# Sensors.net
KiCad netlist of a schematic drawn in Altium Designer
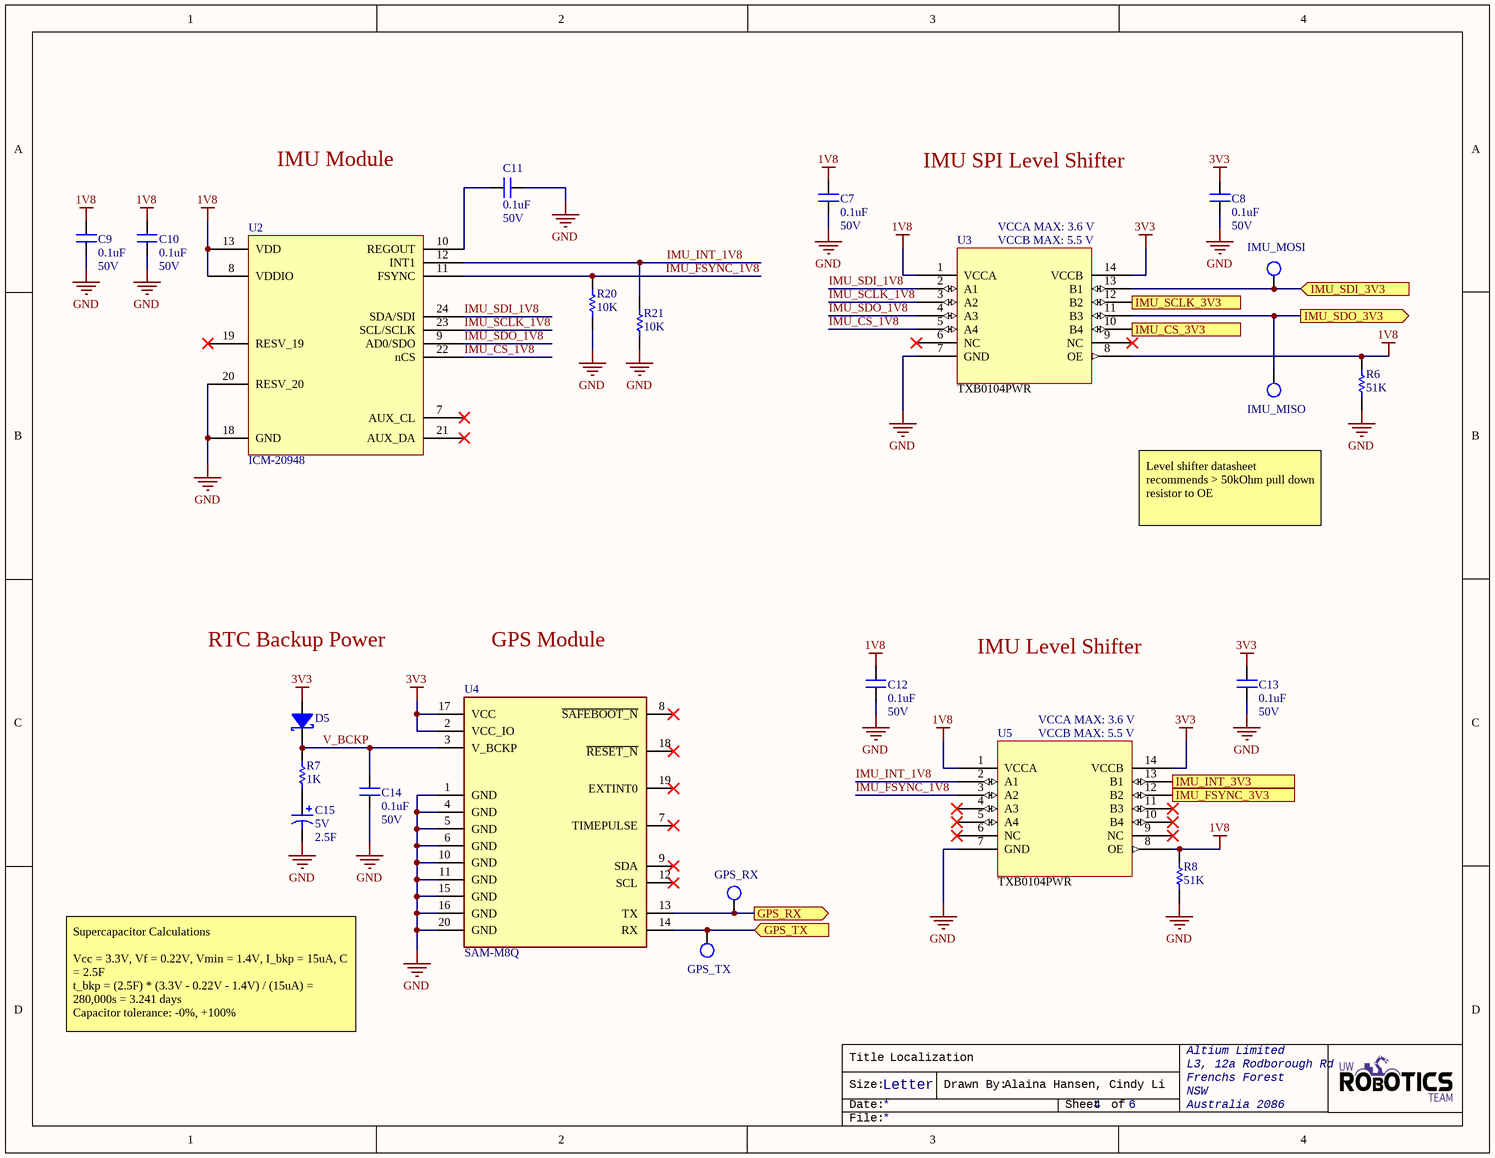
[diagram p0: Sensors.SchDoc]

(export (version "E")
  (design (tool "Eeschema 10.0.6"))
  (components
    (comp (ref "C7")
      (value "0.1uF")
      (footprint "CAPC2012X140N")
      (description "CAP CER 0.1UF 50V X7R 0805")
      (fields
        (field (name "TOLERANCE") "10%")
        (field (name "VOLTAGE RATING") "50V")
        (field (name "Comment") "CAP_0.1uF_50V_0805")
      )
      (libsource (lib "UWRT_Schematic_Library_2020") (part "CAP_0.1uF_50V_0805"))
    )
    (comp (ref "C8")
      (value "0.1uF")
      (footprint "CAPC2012X140N")
      (description "CAP CER 0.1UF 50V X7R 0805")
      (fields
        (field (name "TOLERANCE") "10%")
        (field (name "VOLTAGE RATING") "50V")
        (field (name "Comment") "CAP_0.1uF_50V_0805")
      )
      (libsource (lib "UWRT_Schematic_Library_2020") (part "CAP_0.1uF_50V_0805"))
    )
    (comp (ref "C9")
      (value "0.1uF")
      (footprint "CAPC2012X140N")
      (description "CAP CER 0.1UF 50V X7R 0805")
      (fields
        (field (name "TOLERANCE") "10%")
        (field (name "VOLTAGE RATING") "50V")
        (field (name "Comment") "CAP_0.1uF_50V_0805")
      )
      (libsource (lib "UWRT_Schematic_Library_2020") (part "CAP_0.1uF_50V_0805"))
    )
    (comp (ref "C10")
      (value "0.1uF")
      (footprint "CAPC2012X140N")
      (description "CAP CER 0.1UF 50V X7R 0805")
      (fields
        (field (name "TOLERANCE") "10%")
        (field (name "VOLTAGE RATING") "50V")
        (field (name "Comment") "CAP_0.1uF_50V_0805")
      )
      (libsource (lib "UWRT_Schematic_Library_2020") (part "CAP_0.1uF_50V_0805"))
    )
    (comp (ref "C11")
      (value "0.1uF")
      (footprint "CAPC2012X140N")
      (description "CAP CER 0.1UF 50V X7R 0805")
      (fields
        (field (name "TOLERANCE") "10%")
        (field (name "VOLTAGE RATING") "50V")
        (field (name "Comment") "CAP_0.1uF_50V_0805")
      )
      (libsource (lib "UWRT_Schematic_Library_2020") (part "CAP_0.1uF_50V_0805"))
    )
    (comp (ref "C12")
      (value "0.1uF")
      (footprint "CAPC2012X140N")
      (description "CAP CER 0.1UF 50V X7R 0805")
      (fields
        (field (name "TOLERANCE") "10%")
        (field (name "VOLTAGE RATING") "50V")
        (field (name "Comment") "CAP_0.1uF_50V_0805")
      )
      (libsource (lib "UWRT_Schematic_Library_2020") (part "CAP_0.1uF_50V_0805"))
    )
    (comp (ref "C13")
      (value "0.1uF")
      (footprint "CAPC2012X140N")
      (description "CAP CER 0.1UF 50V X7R 0805")
      (fields
        (field (name "TOLERANCE") "10%")
        (field (name "VOLTAGE RATING") "50V")
        (field (name "Comment") "CAP_0.1uF_50V_0805")
      )
      (libsource (lib "UWRT_Schematic_Library_2020") (part "CAP_0.1uF_50V_0805"))
    )
    (comp (ref "C14")
      (value "0.1uF")
      (footprint "CAPC2012X140N")
      (description "CAP CER 0.1UF 50V X7R 0805")
      (fields
        (field (name "TOLERANCE") "10%")
        (field (name "VOLTAGE RATING") "50V")
        (field (name "Comment") "CAP_0.1uF_50V_0805")
      )
      (libsource (lib "UWRT_Schematic_Library_2020") (part "CAP_0.1uF_50V_0805"))
    )
    (comp (ref "C15")
      (value "CAP_2.5F_5V")
      (description "CAP 2.5F 5V")
      (fields
        (field (name "TOLERANCE") "0%, +100%")
        (field (name "VOLTAGE RATING") "5V")
        (field (name "CAPACITANCE") "2.5F")
      )
      (libsource (lib "UWRT_Schematic_Library_2020") (part "CAP_2.5F_5V"))
    )
    (comp (ref "D5")
      (value "DIO_SCHOTTKY_30V_800mA")
      (footprint "DIO_CUS520,H3F")
      (description "DIODE SCHOTTKY 30V 800MA USC")
      (libsource (lib "UWRT_Schematic_Library_2020") (part "DIO_SCHOTTKY_30V_800mA"))
    )
    (comp (ref "GPS_RX")
      (value "TESTPOINT_LOOP")
      (footprint "TESTPOINT_LOOP")
      (description "Loop testpoint through-hole pad")
      (libsource (lib "UWRT_Schematic_Library_2020") (part "TESTPOINT_LOOP"))
    )
    (comp (ref "GPS_TX")
      (value "TESTPOINT_LOOP")
      (footprint "TESTPOINT_LOOP")
      (description "Loop testpoint through-hole pad")
      (libsource (lib "UWRT_Schematic_Library_2020") (part "TESTPOINT_LOOP"))
    )
    (comp (ref "IMU_MISO")
      (value "TESTPOINT_LOOP")
      (footprint "TESTPOINT_LOOP")
      (description "Loop testpoint through-hole pad")
      (libsource (lib "UWRT_Schematic_Library_2020") (part "TESTPOINT_LOOP"))
    )
    (comp (ref "IMU_MOSI")
      (value "TESTPOINT_LOOP")
      (footprint "TESTPOINT_LOOP")
      (description "Loop testpoint through-hole pad")
      (libsource (lib "UWRT_Schematic_Library_2020") (part "TESTPOINT_LOOP"))
    )
    (comp (ref "R6")
      (value "51K")
      (footprint "RESC1608X55N")
      (description "RES SMD 51K OHM 5% 1/10W 0603")
      (fields (field (name "TOLERANCE") "5%") (field (name "Comment") "RES_51K_0603"))
      (libsource (lib "UWRT_Schematic_Library_2020") (part "RES_51K_0603"))
    )
    (comp (ref "R7")
      (value "1K")
      (footprint "RESC0603(1608)_N")
      (description "RES SMD 1K OHM 5% 1/10W 0603")
      (fields (field (name "TOLERANCE") "5%") (field (name "Comment") "RES_1K_0603"))
      (libsource (lib "UWRT_Schematic_Library_2020") (part "RES_1K_0603"))
    )
    (comp (ref "R8")
      (value "51K")
      (footprint "RESC1608X55N")
      (description "RES SMD 51K OHM 5% 1/10W 0603")
      (fields (field (name "TOLERANCE") "5%") (field (name "Comment") "RES_51K_0603"))
      (libsource (lib "UWRT_Schematic_Library_2020") (part "RES_51K_0603"))
    )
    (comp (ref "R20")
      (value "10K")
      (footprint "RESC0603(1608)_N")
      (description "RES SMD 10K OHM 5% 1/10W 0603")
      (fields (field (name "TOLERANCE") "5%") (field (name "Comment") "RES_10K_0603"))
      (libsource (lib "UWRT_Schematic_Library_2020") (part "RES_10K_0603"))
    )
    (comp (ref "R21")
      (value "10K")
      (footprint "RESC0603(1608)_N")
      (description "RES SMD 10K OHM 5% 1/10W 0603")
      (fields (field (name "TOLERANCE") "5%") (field (name "Comment") "RES_10K_0603"))
      (libsource (lib "UWRT_Schematic_Library_2020") (part "RES_10K_0603"))
    )
    (comp (ref "U2")
      (value "IC_9DOF_IMU")
      (footprint "ICM-20948")
      (description "IMU ACCEL/GYRO/COMPI2C/SPI 24QFN")
      (fields
        (field (name "MANUFACTURER") "TDK InvenSense")
        (field (name "MANUFACTURER PART NUMBER") "ICM-20948")
      )
      (libsource (lib "UWRT_Schematic_Library_2020") (part "IC_9DOF_IMU"))
    )
    (comp (ref "U3")
      (value "TXB0104PWR")
      (footprint "UWRT_Footprint_Library_2020:PW14")
      (fields
        (field (name "MANUFACTURER_PART_NUMBER") "TXB0104PWR")
        (field (name "GENERIC_PART_NUMBER") "TXB0104")
        (field (name "MANUFACTURER") "Texas Instruments")
        (field (name "VCCB MAX") "VCCB MAX: 5.5 V")
        (field (name "VCCA MAX") "VCCA MAX: 3.6 V")
      )
      (libsource (lib "UWRT_Schematic_Library_2020") (part "IC_4CH_LVL_SHIFTER"))
    )
    (comp (ref "U4")
      (value "SAM-M8Q")
      (description "Rf Rx Galileo 1.575GHZ/1.602GHZ")
      (libsource (lib "UWRT_Schematic_Library_2020") (part "SAM-M8Q"))
    )
    (comp (ref "U5")
      (value "TXB0104PWR")
      (footprint "UWRT_Footprint_Library_2020:PW14")
      (fields
        (field (name "MANUFACTURER_PART_NUMBER") "TXB0104PWR")
        (field (name "GENERIC_PART_NUMBER") "TXB0104")
        (field (name "MANUFACTURER") "Texas Instruments")
        (field (name "VCCB MAX") "VCCB MAX: 5.5 V")
        (field (name "VCCA MAX") "VCCA MAX: 3.6 V")
      )
      (libsource (lib "UWRT_Schematic_Library_2020") (part "IC_4CH_LVL_SHIFTER"))
    )
  )
  (nets
    (net (code "1") (name "/GPS_RX") (class "Default")
      (node (ref "GPS_RX") (pin "1") (pintype "passive"))
      (node (ref "U4") (pin "13") (pinfunction "TX_13") (pintype "passive"))
    )
    (net (code "2") (name "/GPS_TX") (class "Default")
      (node (ref "GPS_TX") (pin "1") (pintype "passive"))
      (node (ref "U4") (pin "14") (pinfunction "RX_14") (pintype "passive"))
    )
    (net (code "3") (name "/IMU_CS_1V8") (class "Default")
      (node (ref "U2") (pin "22") (pinfunction "nCS_22") (pintype "passive"))
      (node (ref "U3") (pin "5") (pinfunction "A4_5") (pintype "bidirectional"))
    )
    (net (code "4") (name "/IMU_CS_3V3") (class "Default")
      (node (ref "U3") (pin "10") (pinfunction "B4_10") (pintype "bidirectional"))
    )
    (net (code "5") (name "/IMU_FSYNC_1V8") (class "Default")
      (node (ref "R20") (pin "2") (pinfunction "2_2") (pintype "passive"))
      (node (ref "U2") (pin "11") (pinfunction "FSYNC_11") (pintype "passive"))
      (node (ref "U5") (pin "3") (pinfunction "A2_3") (pintype "bidirectional"))
    )
    (net (code "6") (name "/IMU_FSYNC_3V3") (class "Default")
      (node (ref "U5") (pin "12") (pinfunction "B2_12") (pintype "bidirectional"))
    )
    (net (code "7") (name "/IMU_INT_1V8") (class "Default")
      (node (ref "R21") (pin "2") (pinfunction "2_2") (pintype "passive"))
      (node (ref "U2") (pin "12") (pinfunction "INT1_12") (pintype "passive"))
      (node (ref "U5") (pin "2") (pinfunction "A1_2") (pintype "bidirectional"))
    )
    (net (code "8") (name "/IMU_INT_3V3") (class "Default")
      (node (ref "U5") (pin "13") (pinfunction "B1_13") (pintype "bidirectional"))
    )
    (net (code "9") (name "/IMU_SCLK_1V8") (class "Default")
      (node (ref "U2") (pin "23") (pinfunction "SCL/SCLK_23") (pintype "passive"))
      (node (ref "U3") (pin "3") (pinfunction "A2_3") (pintype "bidirectional"))
    )
    (net (code "10") (name "/IMU_SCLK_3V3") (class "Default")
      (node (ref "U3") (pin "12") (pinfunction "B2_12") (pintype "bidirectional"))
    )
    (net (code "11") (name "/IMU_SDI_1V8") (class "Default")
      (node (ref "U2") (pin "24") (pinfunction "SDA/SDI_24") (pintype "passive"))
      (node (ref "U3") (pin "2") (pinfunction "A1_2") (pintype "bidirectional"))
    )
    (net (code "12") (name "/IMU_SDI_3V3") (class "Default")
      (node (ref "IMU_MOSI") (pin "1") (pintype "passive"))
      (node (ref "U3") (pin "13") (pinfunction "B1_13") (pintype "bidirectional"))
    )
    (net (code "13") (name "/IMU_SDO_1V8") (class "Default")
      (node (ref "U2") (pin "9") (pinfunction "AD0/SDO_9") (pintype "passive"))
      (node (ref "U3") (pin "4") (pinfunction "A3_4") (pintype "bidirectional"))
    )
    (net (code "14") (name "/IMU_SDO_3V3") (class "Default")
      (node (ref "IMU_MISO") (pin "1") (pintype "passive"))
      (node (ref "U3") (pin "11") (pinfunction "B3_11") (pintype "bidirectional"))
    )
    (net (code "15") (name "/V_BCKP") (class "Default")
      (node (ref "C14") (pin "2") (pinfunction "2_2") (pintype "passive"))
      (node (ref "D5") (pin "2") (pinfunction "Cathode_2") (pintype "passive"))
      (node (ref "R7") (pin "1") (pinfunction "1_1") (pintype "passive"))
      (node (ref "U4") (pin "3") (pinfunction "V_BCKP_3") (pintype "power_in"))
    )
    (net (code "16") (name "1V8") (class "Default")
      (node (ref "C10") (pin "2") (pinfunction "2_2") (pintype "passive"))
      (node (ref "C12") (pin "2") (pinfunction "2_2") (pintype "passive"))
      (node (ref "C7") (pin "2") (pinfunction "2_2") (pintype "passive"))
      (node (ref "C9") (pin "2") (pinfunction "2_2") (pintype "passive"))
      (node (ref "R6") (pin "2") (pinfunction "2_2") (pintype "passive"))
      (node (ref "R8") (pin "2") (pinfunction "2_2") (pintype "passive"))
      (node (ref "U2") (pin "13") (pinfunction "VDD_13") (pintype "passive"))
      (node (ref "U2") (pin "8") (pinfunction "VDDIO_8") (pintype "passive"))
      (node (ref "U3") (pin "1") (pinfunction "VCCA_1") (pintype "power_in"))
      (node (ref "U3") (pin "8") (pinfunction "OE_8") (pintype "output"))
      (node (ref "U5") (pin "1") (pinfunction "VCCA_1") (pintype "power_in"))
      (node (ref "U5") (pin "8") (pinfunction "OE_8") (pintype "output"))
    )
    (net (code "17") (name "3V3") (class "Default")
      (node (ref "C13") (pin "2") (pinfunction "2_2") (pintype "passive"))
      (node (ref "C8") (pin "2") (pinfunction "2_2") (pintype "passive"))
      (node (ref "D5") (pin "1") (pinfunction "Anode_1") (pintype "passive"))
      (node (ref "U3") (pin "14") (pinfunction "VCCB_14") (pintype "power_in"))
      (node (ref "U4") (pin "17") (pinfunction "VCC_17") (pintype "power_in"))
      (node (ref "U4") (pin "2") (pinfunction "VCC_IO_2") (pintype "power_in"))
      (node (ref "U5") (pin "14") (pinfunction "VCCB_14") (pintype "power_in"))
    )
    (net (code "18") (name "GND") (class "Default")
      (node (ref "C10") (pin "1") (pinfunction "1_1") (pintype "passive"))
      (node (ref "C11") (pin "2") (pinfunction "2_2") (pintype "passive"))
      (node (ref "C12") (pin "1") (pinfunction "1_1") (pintype "passive"))
      (node (ref "C13") (pin "1") (pinfunction "1_1") (pintype "passive"))
      (node (ref "C14") (pin "1") (pinfunction "1_1") (pintype "passive"))
      (node (ref "C15") (pin "2") (pinfunction "2_2") (pintype "passive"))
      (node (ref "C7") (pin "1") (pinfunction "1_1") (pintype "passive"))
      (node (ref "C8") (pin "1") (pinfunction "1_1") (pintype "passive"))
      (node (ref "C9") (pin "1") (pinfunction "1_1") (pintype "passive"))
      (node (ref "R20") (pin "1") (pinfunction "1_1") (pintype "passive"))
      (node (ref "R21") (pin "1") (pinfunction "1_1") (pintype "passive"))
      (node (ref "R6") (pin "1") (pinfunction "1_1") (pintype "passive"))
      (node (ref "R8") (pin "1") (pinfunction "1_1") (pintype "passive"))
      (node (ref "U2") (pin "18") (pinfunction "GND_18") (pintype "passive"))
      (node (ref "U2") (pin "20") (pinfunction "RESV_20_20") (pintype "passive"))
      (node (ref "U3") (pin "7") (pinfunction "GND_7") (pintype "power_in"))
      (node (ref "U4") (pin "1") (pinfunction "GND_1") (pintype "power_in"))
      (node (ref "U4") (pin "10") (pinfunction "GND_10") (pintype "power_in"))
      (node (ref "U4") (pin "11") (pinfunction "GND_11") (pintype "power_in"))
      (node (ref "U4") (pin "15") (pinfunction "GND_15") (pintype "power_in"))
      (node (ref "U4") (pin "16") (pinfunction "GND_16") (pintype "power_in"))
      (node (ref "U4") (pin "20") (pinfunction "GND_20") (pintype "power_in"))
      (node (ref "U4") (pin "4") (pinfunction "GND_4") (pintype "power_in"))
      (node (ref "U4") (pin "5") (pinfunction "GND_5") (pintype "power_in"))
      (node (ref "U4") (pin "6") (pinfunction "GND_6") (pintype "power_in"))
      (node (ref "U5") (pin "7") (pinfunction "GND_7") (pintype "power_in"))
    )
    (net (code "19") (name "Net-(C15-Pad1)") (class "Default")
      (node (ref "C15") (pin "1") (pinfunction "1_1") (pintype "passive"))
      (node (ref "R7") (pin "2") (pinfunction "2_2") (pintype "passive"))
    )
    (net (code "20") (name "Net-(U2-REGOUT)") (class "Default")
      (node (ref "C11") (pin "1") (pinfunction "1_1") (pintype "passive"))
      (node (ref "U2") (pin "10") (pinfunction "REGOUT_10") (pintype "passive"))
    )
    (net (code "21") (name "unconnected-(U2-AUX_CL-Pad7)") (class "Default")
      (node (ref "U2") (pin "7") (pinfunction "AUX_CL_7") (pintype "passive+no_connect"))
    )
    (net (code "22") (name "unconnected-(U2-AUX_DA-Pad21)") (class "Default")
      (node (ref "U2") (pin "21") (pinfunction "AUX_DA_21") (pintype "passive+no_connect"))
    )
    (net (code "23") (name "unconnected-(U2-RESV_19-Pad19)") (class "Default")
      (node (ref "U2") (pin "19") (pinfunction "RESV_19_19") (pintype "passive+no_connect"))
    )
    (net (code "24") (name "unconnected-(U3-NC-Pad6)") (class "Default")
      (node (ref "U3") (pin "6") (pinfunction "NC_6") (pintype "passive+no_connect"))
    )
    (net (code "25") (name "unconnected-(U3-NC-Pad9)") (class "Default")
      (node (ref "U3") (pin "9") (pinfunction "NC_9") (pintype "passive+no_connect"))
    )
    (net (code "26") (name "unconnected-(U4-EXTINT0-Pad19)") (class "Default")
      (node (ref "U4") (pin "19") (pinfunction "EXTINT0_19") (pintype "passive+no_connect"))
    )
    (net (code "27") (name "unconnected-(U4-SCL-Pad12)") (class "Default")
      (node (ref "U4") (pin "12") (pinfunction "SCL_12") (pintype "passive+no_connect"))
    )
    (net (code "28") (name "unconnected-(U4-SDA-Pad9)") (class "Default")
      (node (ref "U4") (pin "9") (pinfunction "SDA_9") (pintype "passive+no_connect"))
    )
    (net (code "29") (name "unconnected-(U4-TIMEPULSE-Pad7)") (class "Default")
      (node (ref "U4") (pin "7") (pinfunction "TIMEPULSE_7") (pintype "passive+no_connect"))
    )
    (net (code "30") (name "unconnected-(U4-~{RESET_N}-Pad18)") (class "Default")
      (node (ref "U4") (pin "18") (pinfunction "~{RESET_N}_18") (pintype "passive+no_connect"))
    )
    (net (code "31") (name "unconnected-(U4-~{SAFEBOOT_N}-Pad8)") (class "Default")
      (node (ref "U4") (pin "8") (pinfunction "~{SAFEBOOT_N}_8") (pintype "passive+no_connect"))
    )
    (net (code "32") (name "unconnected-(U5-A3-Pad4)") (class "Default")
      (node (ref "U5") (pin "4") (pinfunction "A3_4") (pintype "bidirectional+no_connect"))
    )
    (net (code "33") (name "unconnected-(U5-A4-Pad5)") (class "Default")
      (node (ref "U5") (pin "5") (pinfunction "A4_5") (pintype "bidirectional+no_connect"))
    )
    (net (code "34") (name "unconnected-(U5-B3-Pad11)") (class "Default")
      (node (ref "U5") (pin "11") (pinfunction "B3_11") (pintype "bidirectional+no_connect"))
    )
    (net (code "35") (name "unconnected-(U5-B4-Pad10)") (class "Default")
      (node (ref "U5") (pin "10") (pinfunction "B4_10") (pintype "bidirectional+no_connect"))
    )
    (net (code "36") (name "unconnected-(U5-NC-Pad6)") (class "Default")
      (node (ref "U5") (pin "6") (pinfunction "NC_6") (pintype "passive+no_connect"))
    )
    (net (code "37") (name "unconnected-(U5-NC-Pad9)") (class "Default")
      (node (ref "U5") (pin "9") (pinfunction "NC_9") (pintype "passive+no_connect"))
    )
  )
)
